# Pi_grammer_SPEEDY_SPI_V2.net
KiCad netlist of a schematic drawn in EAGLE
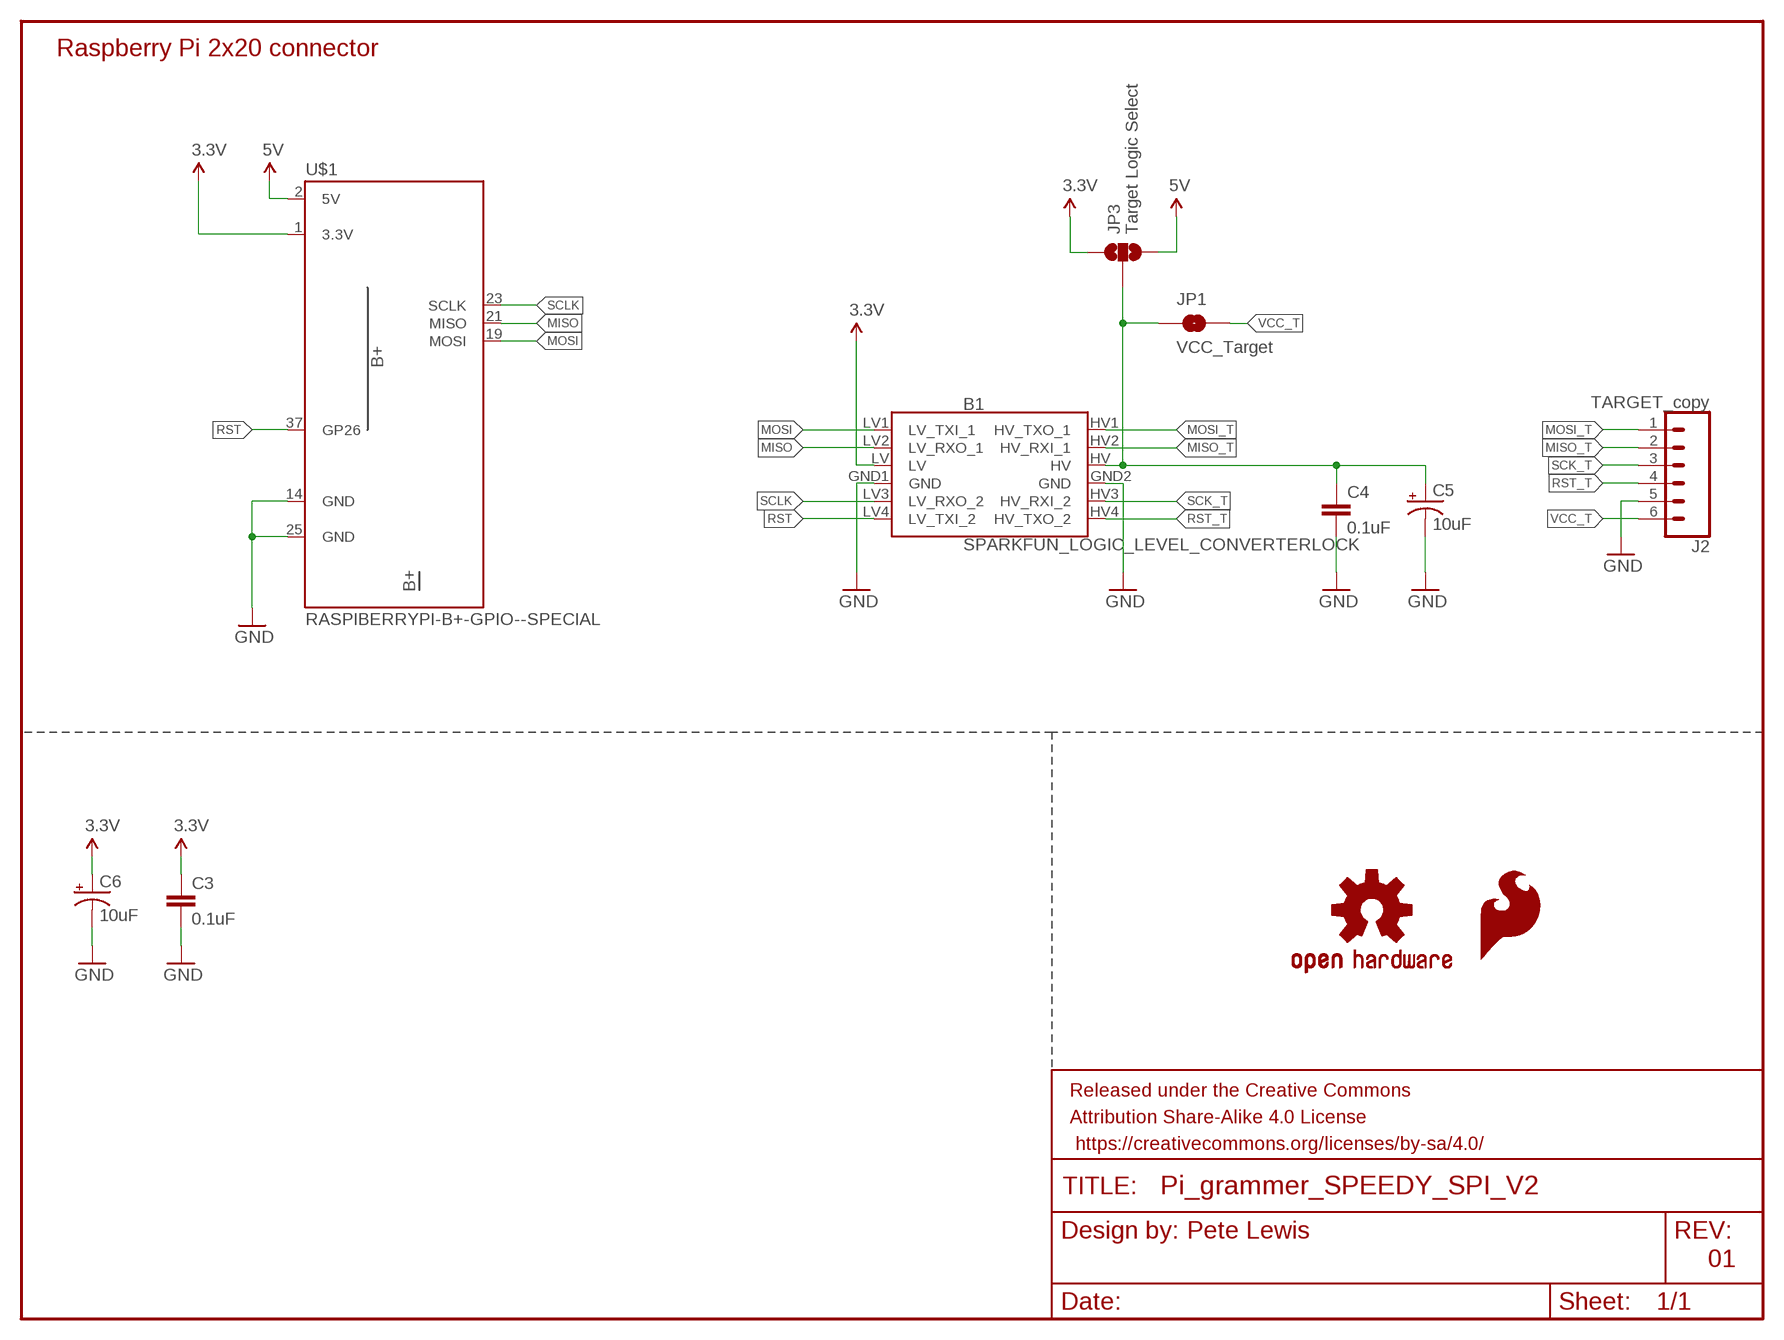
[diagram p0: schematic, sheet 1]

(export (version "E")
  (design (tool "Eeschema 10.0.6"))
  (components
    (comp (ref "B1")
      (value "SPARKFUN_LOGIC_LEVEL_CONVERTERLOCK")
      (footprint "eagle-import:SPARKFUN_LOGIC_LEVEL_CONVERTER_LOCK")
      (libsource (lib "eagle-import") (part "SPARKFUN_LOGIC_LEVEL_CONVERTERLOCK"))
    )
    (comp (ref "C3")
      (value "0.1uF")
      (footprint "eagle-import:0603")
      (libsource (lib "eagle-import") (part "0.1UF-0603-25V-(+80/-20%)"))
    )
    (comp (ref "C4")
      (value "0.1uF")
      (footprint "eagle-import:0603")
      (libsource (lib "eagle-import") (part "0.1UF-0603-25V-(+80/-20%)"))
    )
    (comp (ref "C5")
      (value "10uF")
      (footprint "eagle-import:EIA3216")
      (libsource (lib "eagle-import") (part "10UF-POLAR-EIA3216-16V-10%(TANT)"))
    )
    (comp (ref "C6")
      (value "10uF")
      (footprint "eagle-import:EIA3216")
      (libsource (lib "eagle-import") (part "10UF-POLAR-EIA3216-16V-10%(TANT)"))
    )
    (comp (ref "FRAME1")
      (value "FRAME-LETTER")
      (footprint "eagle-import:CREATIVE_COMMONS")
      (libsource (lib "eagle-import") (part "FRAME-LETTER"))
    )
    (comp (ref "J2")
      (value "TARGET_copy")
      (footprint "eagle-import:1X06-SIP_LOCK")
      (libsource (lib "eagle-import") (part "CONN_06SIP_LOCK"))
    )
    (comp (ref "JP1")
      (value "VCC_Target")
      (footprint "eagle-import:SMT-JUMPER_2_NO_SILK")
      (libsource (lib "eagle-import") (part "JUMPER-SMT_2_NO_SILK"))
    )
    (comp (ref "JP3")
      (value "Target Logic Select")
      (footprint "eagle-import:SMT-JUMPER_3_NO_SILK")
      (libsource (lib "eagle-import") (part "JUMPER-SMT_3_NO_SILK"))
    )
    (comp (ref "LOGO1")
      (value "SFE_LOGO_FLAME.1_INCH")
      (footprint "eagle-import:SFE_LOGO_FLAME_.1")
      (libsource (lib "eagle-import") (part "SFE_LOGO_FLAME.1_INCH"))
    )
    (comp (ref "LOGO2")
      (value "OSHW-LOGOS")
      (footprint "eagle-import:OSHW-LOGO-S")
      (libsource (lib "eagle-import") (part "OSHW-LOGOS"))
    )
    (comp (ref "U$1")
      (value "RASPIBERRYPI-B+-GPIO--SPECIAL")
      (footprint "eagle-import:2X20-SHROUDED--SPECIAL")
      (libsource (lib "eagle-import") (part "RASPIBERRYPI-B+-GPIO--SPECIAL"))
    )
  )
  (nets
    (net (code "1") (name "3.3V") (class "Default")
      (node (ref "B1") (pin "LV") (pinfunction "LV_LV") (pintype "power_in"))
      (node (ref "C3") (pin "1") (pinfunction "1_1") (pintype "passive"))
      (node (ref "C6") (pin "+") (pinfunction "+_+") (pintype "passive"))
      (node (ref "JP3") (pin "1") (pinfunction "1_1") (pintype "passive"))
      (node (ref "U$1") (pin "1") (pinfunction "3.3V_1") (pintype "power_in"))
    )
    (net (code "2") (name "5V") (class "Default")
      (node (ref "JP3") (pin "3") (pinfunction "3_3") (pintype "passive"))
      (node (ref "U$1") (pin "2") (pinfunction "5V_2") (pintype "power_in"))
    )
    (net (code "3") (name "GND") (class "Default")
      (node (ref "B1") (pin "GND1") (pinfunction "GND_GND1") (pintype "power_in"))
      (node (ref "B1") (pin "GND2") (pinfunction "GND_GND2") (pintype "power_in"))
      (node (ref "C3") (pin "2") (pinfunction "2_2") (pintype "passive"))
      (node (ref "C4") (pin "2") (pinfunction "2_2") (pintype "passive"))
      (node (ref "C5") (pin "-") (pinfunction "-_-") (pintype "passive"))
      (node (ref "C6") (pin "-") (pinfunction "-_-") (pintype "passive"))
      (node (ref "J2") (pin "5") (pinfunction "5_5") (pintype "passive"))
      (node (ref "U$1") (pin "14") (pinfunction "GND_14") (pintype "power_in"))
      (node (ref "U$1") (pin "25") (pinfunction "GND_25") (pintype "power_in"))
    )
    (net (code "4") (name "MISO") (class "Default")
      (node (ref "B1") (pin "LV2") (pinfunction "LV_RXO_1_LV2") (pintype "bidirectional"))
      (node (ref "U$1") (pin "21") (pinfunction "MISO_21") (pintype "input"))
    )
    (net (code "5") (name "MISO_T") (class "Default")
      (node (ref "B1") (pin "HV2") (pinfunction "HV_RXI_1_HV2") (pintype "bidirectional"))
      (node (ref "J2") (pin "2") (pinfunction "2_2") (pintype "passive"))
    )
    (net (code "6") (name "MOSI") (class "Default")
      (node (ref "B1") (pin "LV1") (pinfunction "LV_TXI_1_LV1") (pintype "bidirectional"))
      (node (ref "U$1") (pin "19") (pinfunction "MOSI_19") (pintype "output"))
    )
    (net (code "7") (name "MOSI_T") (class "Default")
      (node (ref "B1") (pin "HV1") (pinfunction "HV_TXO_1_HV1") (pintype "bidirectional"))
      (node (ref "J2") (pin "1") (pinfunction "1_1") (pintype "passive"))
    )
    (net (code "8") (name "Net-(B1-PadHV)") (class "Default")
      (node (ref "B1") (pin "HV") (pinfunction "HV_HV") (pintype "power_in"))
      (node (ref "C4") (pin "1") (pinfunction "1_1") (pintype "passive"))
      (node (ref "C5") (pin "+") (pinfunction "+_+") (pintype "passive"))
      (node (ref "JP1") (pin "1") (pinfunction "1_1") (pintype "passive"))
      (node (ref "JP3") (pin "2") (pinfunction "2_2") (pintype "passive"))
    )
    (net (code "9") (name "RST") (class "Default")
      (node (ref "B1") (pin "LV4") (pinfunction "LV_TXI_2_LV4") (pintype "bidirectional"))
      (node (ref "U$1") (pin "37") (pinfunction "GP26_37") (pintype "bidirectional"))
    )
    (net (code "10") (name "RST_T") (class "Default")
      (node (ref "B1") (pin "HV4") (pinfunction "HV_TXO_2_HV4") (pintype "bidirectional"))
      (node (ref "J2") (pin "4") (pinfunction "4_4") (pintype "passive"))
    )
    (net (code "11") (name "SCK_T") (class "Default")
      (node (ref "B1") (pin "HV3") (pinfunction "HV_RXI_2_HV3") (pintype "bidirectional"))
      (node (ref "J2") (pin "3") (pinfunction "3_3") (pintype "passive"))
    )
    (net (code "12") (name "SCLK") (class "Default")
      (node (ref "B1") (pin "LV3") (pinfunction "LV_RXO_2_LV3") (pintype "bidirectional"))
      (node (ref "U$1") (pin "23") (pinfunction "SCLK_23") (pintype "output"))
    )
    (net (code "13") (name "VCC_T") (class "Default")
      (node (ref "J2") (pin "6") (pinfunction "6_6") (pintype "passive"))
      (node (ref "JP1") (pin "2") (pinfunction "2_2") (pintype "passive"))
    )
  )
)
